# swarm_circuit.net
KiCad netlist of a schematic drawn in EAGLE
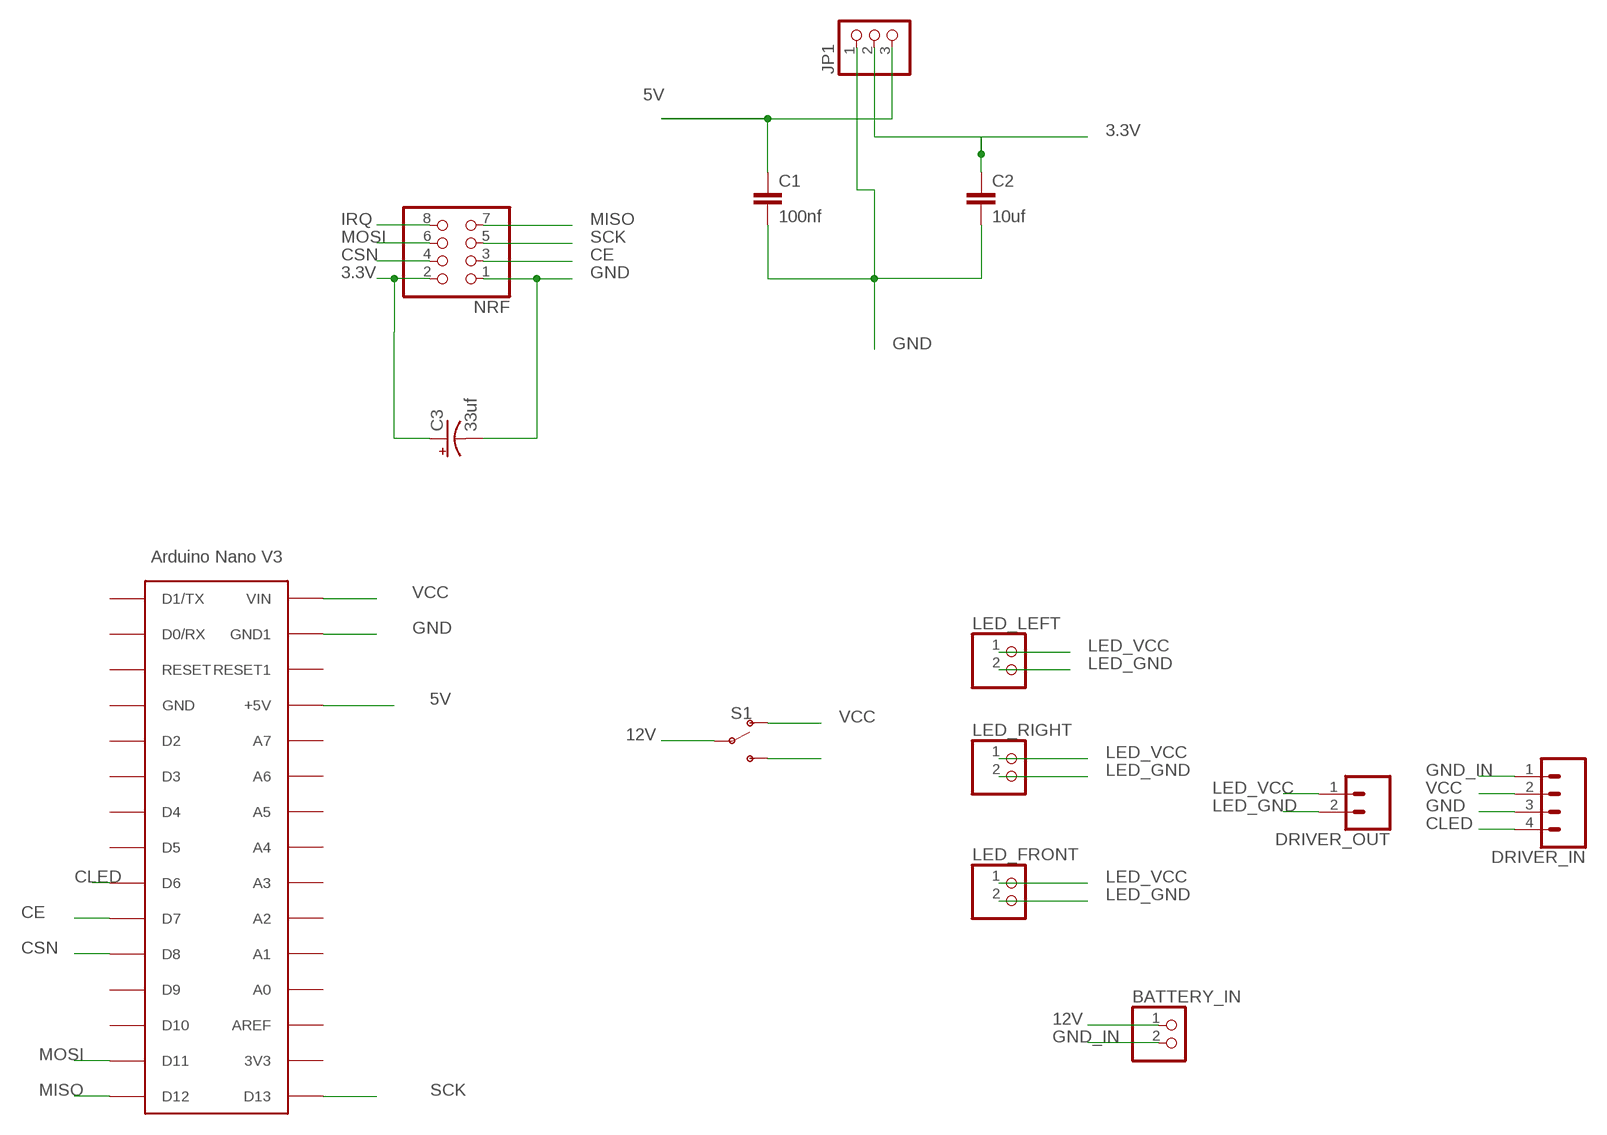
[diagram p0: schematic, sheet 1]

(export (version "E")
  (design (tool "Eeschema 10.0.6"))
  (components
    (comp (ref "BATTERY_IN")
      (value "HEADER-1X2ROUND")
      (footprint "eagle-import:1X02_ROUND")
      (libsource (lib "eagle-import") (part "HEADER-1X2ROUND"))
    )
    (comp (ref "C1")
      (value "100nf")
      (footprint "eagle-import:CAP-PTH-SMALL-KIT")
      (libsource (lib "eagle-import") (part "0.1UF-KIT-EZ-50V-20%"))
    )
    (comp (ref "C2")
      (value "10uf")
      (footprint "eagle-import:CAP-PTH-SMALL-KIT")
      (libsource (lib "eagle-import") (part "0.1UF-KIT-EZ-50V-20%"))
    )
    (comp (ref "C3")
      (value "33uf")
      (footprint "eagle-import:CPOL-RADIAL-5MM-10MM-KIT")
      (libsource (lib "eagle-import") (part "1000UF-RADIAL-5MM-35V-20%-KIT"))
    )
    (comp (ref "DRIVER_IN")
      (value "CONN_04")
      (footprint "eagle-import:1X04")
      (libsource (lib "eagle-import") (part "CONN_04"))
    )
    (comp (ref "DRIVER_OUT")
      (value "CONN_02")
      (footprint "eagle-import:1X02")
      (libsource (lib "eagle-import") (part "CONN_02"))
    )
    (comp (ref "JP1")
      (value "PINHD-1X3")
      (footprint "eagle-import:1X03")
      (libsource (lib "eagle-import") (part "PINHD-1X3"))
    )
    (comp (ref "LED_FRONT")
      (value "HEADER-1X2ROUND")
      (footprint "eagle-import:1X02_ROUND")
      (libsource (lib "eagle-import") (part "HEADER-1X2ROUND"))
    )
    (comp (ref "LED_LEFT")
      (value "HEADER-1X2ROUND")
      (footprint "eagle-import:1X02_ROUND")
      (libsource (lib "eagle-import") (part "HEADER-1X2ROUND"))
    )
    (comp (ref "LED_RIGHT")
      (value "HEADER-1X2ROUND")
      (footprint "eagle-import:1X02_ROUND")
      (libsource (lib "eagle-import") (part "HEADER-1X2ROUND"))
    )
    (comp (ref "NRF")
      (value "PINHD-2X4")
      (footprint "eagle-import:2X04")
      (libsource (lib "eagle-import") (part "PINHD-2X4"))
    )
    (comp (ref "S1")
      (value "SWITCH-SPDT-PTH-11.6X4.0MM")
      (footprint "eagle-import:SWITCH_SPDT_PTH_11.6X4.0MM")
      (libsource (lib "eagle-import") (part "SWITCH-SPDT-PTH-11.6X4.0MM"))
    )
    (comp (ref "U$1")
      (value "ARDUINONANO")
      (footprint "eagle-import:PDIP-32")
      (libsource (lib "eagle-import") (part "ARDUINONANO"))
    )
  )
  (nets
    (net (code "1") (name "/3.3V") (class "Default")
      (node (ref "C2") (pin "1") (pinfunction "1_1") (pintype "passive"))
      (node (ref "C3") (pin "+") (pinfunction "+_+") (pintype "passive"))
      (node (ref "JP1") (pin "2") (pinfunction "2_2") (pintype "passive"))
      (node (ref "NRF") (pin "2") (pinfunction "2_2") (pintype "passive"))
    )
    (net (code "2") (name "/5V") (class "Default")
      (node (ref "C1") (pin "1") (pinfunction "1_1") (pintype "passive"))
      (node (ref "JP1") (pin "3") (pinfunction "3_3") (pintype "passive"))
      (node (ref "U$1") (pin "+5V") (pinfunction "+5V_+5V") (pintype "bidirectional"))
    )
    (net (code "3") (name "/12V") (class "Default")
      (node (ref "BATTERY_IN") (pin "1") (pinfunction "1_1") (pintype "passive"))
      (node (ref "S1") (pin "2") (pinfunction "P_2") (pintype "passive"))
    )
    (net (code "4") (name "/CE") (class "Default")
      (node (ref "NRF") (pin "3") (pinfunction "3_3") (pintype "passive"))
      (node (ref "U$1") (pin "D7") (pinfunction "D7_D7") (pintype "bidirectional"))
    )
    (net (code "5") (name "/CLED") (class "Default")
      (node (ref "DRIVER_IN") (pin "4") (pinfunction "4_4") (pintype "passive"))
      (node (ref "U$1") (pin "D6") (pinfunction "D6_D6") (pintype "bidirectional"))
    )
    (net (code "6") (name "/CSN") (class "Default")
      (node (ref "NRF") (pin "4") (pinfunction "4_4") (pintype "passive"))
      (node (ref "U$1") (pin "D8") (pinfunction "D8_D8") (pintype "bidirectional"))
    )
    (net (code "7") (name "/GND") (class "Default")
      (node (ref "C1") (pin "2") (pinfunction "2_2") (pintype "passive"))
      (node (ref "C2") (pin "2") (pinfunction "2_2") (pintype "passive"))
      (node (ref "C3") (pin "-") (pinfunction "-_-") (pintype "passive"))
      (node (ref "DRIVER_IN") (pin "3") (pinfunction "3_3") (pintype "passive"))
      (node (ref "JP1") (pin "1") (pinfunction "1_1") (pintype "passive"))
      (node (ref "NRF") (pin "1") (pinfunction "1_1") (pintype "passive"))
      (node (ref "U$1") (pin "GND1") (pinfunction "GND1_GND1") (pintype "bidirectional"))
    )
    (net (code "8") (name "/GND_IN") (class "Default")
      (node (ref "BATTERY_IN") (pin "2") (pinfunction "2_2") (pintype "passive"))
      (node (ref "DRIVER_IN") (pin "1") (pinfunction "1_1") (pintype "passive"))
    )
    (net (code "9") (name "/IRQ") (class "Default")
      (node (ref "NRF") (pin "8") (pinfunction "8_8") (pintype "passive"))
    )
    (net (code "10") (name "/LED_GND") (class "Default")
      (node (ref "DRIVER_OUT") (pin "2") (pinfunction "2_2") (pintype "passive"))
      (node (ref "LED_FRONT") (pin "2") (pinfunction "2_2") (pintype "passive"))
      (node (ref "LED_LEFT") (pin "2") (pinfunction "2_2") (pintype "passive"))
      (node (ref "LED_RIGHT") (pin "2") (pinfunction "2_2") (pintype "passive"))
    )
    (net (code "11") (name "/LED_VCC") (class "Default")
      (node (ref "DRIVER_OUT") (pin "1") (pinfunction "1_1") (pintype "passive"))
      (node (ref "LED_FRONT") (pin "1") (pinfunction "1_1") (pintype "passive"))
      (node (ref "LED_LEFT") (pin "1") (pinfunction "1_1") (pintype "passive"))
      (node (ref "LED_RIGHT") (pin "1") (pinfunction "1_1") (pintype "passive"))
    )
    (net (code "12") (name "/MISO") (class "Default")
      (node (ref "NRF") (pin "7") (pinfunction "7_7") (pintype "passive"))
      (node (ref "U$1") (pin "D12") (pinfunction "D12_D12") (pintype "bidirectional"))
    )
    (net (code "13") (name "/MOSI") (class "Default")
      (node (ref "NRF") (pin "6") (pinfunction "6_6") (pintype "passive"))
      (node (ref "U$1") (pin "D11") (pinfunction "D11_D11") (pintype "bidirectional"))
    )
    (net (code "14") (name "/SCK") (class "Default")
      (node (ref "NRF") (pin "5") (pinfunction "5_5") (pintype "passive"))
      (node (ref "U$1") (pin "D13") (pinfunction "D13_D13") (pintype "bidirectional"))
    )
    (net (code "15") (name "/VCC") (class "Default")
      (node (ref "DRIVER_IN") (pin "2") (pinfunction "2_2") (pintype "passive"))
      (node (ref "S1") (pin "1") (pinfunction "O_1") (pintype "passive"))
      (node (ref "S1") (pin "3") (pinfunction "S_3") (pintype "passive"))
      (node (ref "U$1") (pin "VIN") (pinfunction "VIN_VIN") (pintype "bidirectional"))
    )
    (net (code "16") (name "unconnected-(U$1-A0-PadA7)") (class "Default")
      (node (ref "U$1") (pin "A7") (pinfunction "A0_A7") (pintype "bidirectional"))
    )
    (net (code "17") (name "unconnected-(U$1-A1-PadA6)") (class "Default")
      (node (ref "U$1") (pin "A6") (pinfunction "A1_A6") (pintype "bidirectional"))
    )
    (net (code "18") (name "unconnected-(U$1-A2-PadA5)") (class "Default")
      (node (ref "U$1") (pin "A5") (pinfunction "A2_A5") (pintype "bidirectional"))
    )
    (net (code "19") (name "unconnected-(U$1-A3-PadA4)") (class "Default")
      (node (ref "U$1") (pin "A4") (pinfunction "A3_A4") (pintype "bidirectional"))
    )
    (net (code "20") (name "unconnected-(U$1-A4-PadA3)") (class "Default")
      (node (ref "U$1") (pin "A3") (pinfunction "A4_A3") (pintype "bidirectional"))
    )
    (net (code "21") (name "unconnected-(U$1-A5-PadA2)") (class "Default")
      (node (ref "U$1") (pin "A2") (pinfunction "A5_A2") (pintype "bidirectional"))
    )
    (net (code "22") (name "unconnected-(U$1-A6-PadA1)") (class "Default")
      (node (ref "U$1") (pin "A1") (pinfunction "A6_A1") (pintype "bidirectional"))
    )
    (net (code "23") (name "unconnected-(U$1-A7-PadA0)") (class "Default")
      (node (ref "U$1") (pin "A0") (pinfunction "A7_A0") (pintype "bidirectional"))
    )
    (net (code "24") (name "unconnected-(U$1-Pad3V3)") (class "Default")
      (node (ref "U$1") (pin "3V3") (pinfunction "3V3_3V3") (pintype "bidirectional"))
    )
    (net (code "25") (name "unconnected-(U$1-PadAREF)") (class "Default")
      (node (ref "U$1") (pin "AREF") (pinfunction "AREF_AREF") (pintype "bidirectional"))
    )
    (net (code "26") (name "unconnected-(U$1-PadD0{slash}RX)") (class "Default")
      (node (ref "U$1") (pin "D0/RX") (pinfunction "D0/RX_D0/RX") (pintype "bidirectional"))
    )
    (net (code "27") (name "unconnected-(U$1-PadD1{slash}TX)") (class "Default")
      (node (ref "U$1") (pin "D1/TX") (pinfunction "D1/TX_D1/TX") (pintype "bidirectional"))
    )
    (net (code "28") (name "unconnected-(U$1-PadD2)") (class "Default")
      (node (ref "U$1") (pin "D2") (pinfunction "D2_D2") (pintype "bidirectional"))
    )
    (net (code "29") (name "unconnected-(U$1-PadD3)") (class "Default")
      (node (ref "U$1") (pin "D3") (pinfunction "D3_D3") (pintype "bidirectional"))
    )
    (net (code "30") (name "unconnected-(U$1-PadD4)") (class "Default")
      (node (ref "U$1") (pin "D4") (pinfunction "D4_D4") (pintype "bidirectional"))
    )
    (net (code "31") (name "unconnected-(U$1-PadD5)") (class "Default")
      (node (ref "U$1") (pin "D5") (pinfunction "D5_D5") (pintype "bidirectional"))
    )
    (net (code "32") (name "unconnected-(U$1-PadD9)") (class "Default")
      (node (ref "U$1") (pin "D9") (pinfunction "D9_D9") (pintype "bidirectional"))
    )
    (net (code "33") (name "unconnected-(U$1-PadD10)") (class "Default")
      (node (ref "U$1") (pin "D10") (pinfunction "D10_D10") (pintype "bidirectional"))
    )
    (net (code "34") (name "unconnected-(U$1-PadGND)") (class "Default")
      (node (ref "U$1") (pin "GND") (pinfunction "GND_GND") (pintype "bidirectional"))
    )
    (net (code "35") (name "unconnected-(U$1-PadRESET)") (class "Default")
      (node (ref "U$1") (pin "RESET") (pinfunction "RESET_RESET") (pintype "bidirectional"))
    )
    (net (code "36") (name "unconnected-(U$1-PadRESET1)") (class "Default")
      (node (ref "U$1") (pin "RESET1") (pinfunction "RESET1_RESET1") (pintype "bidirectional"))
    )
  )
)
